# Copy_of_Copy_of_Sheet1.net
KiCad netlist of a schematic drawn in Altium Designer
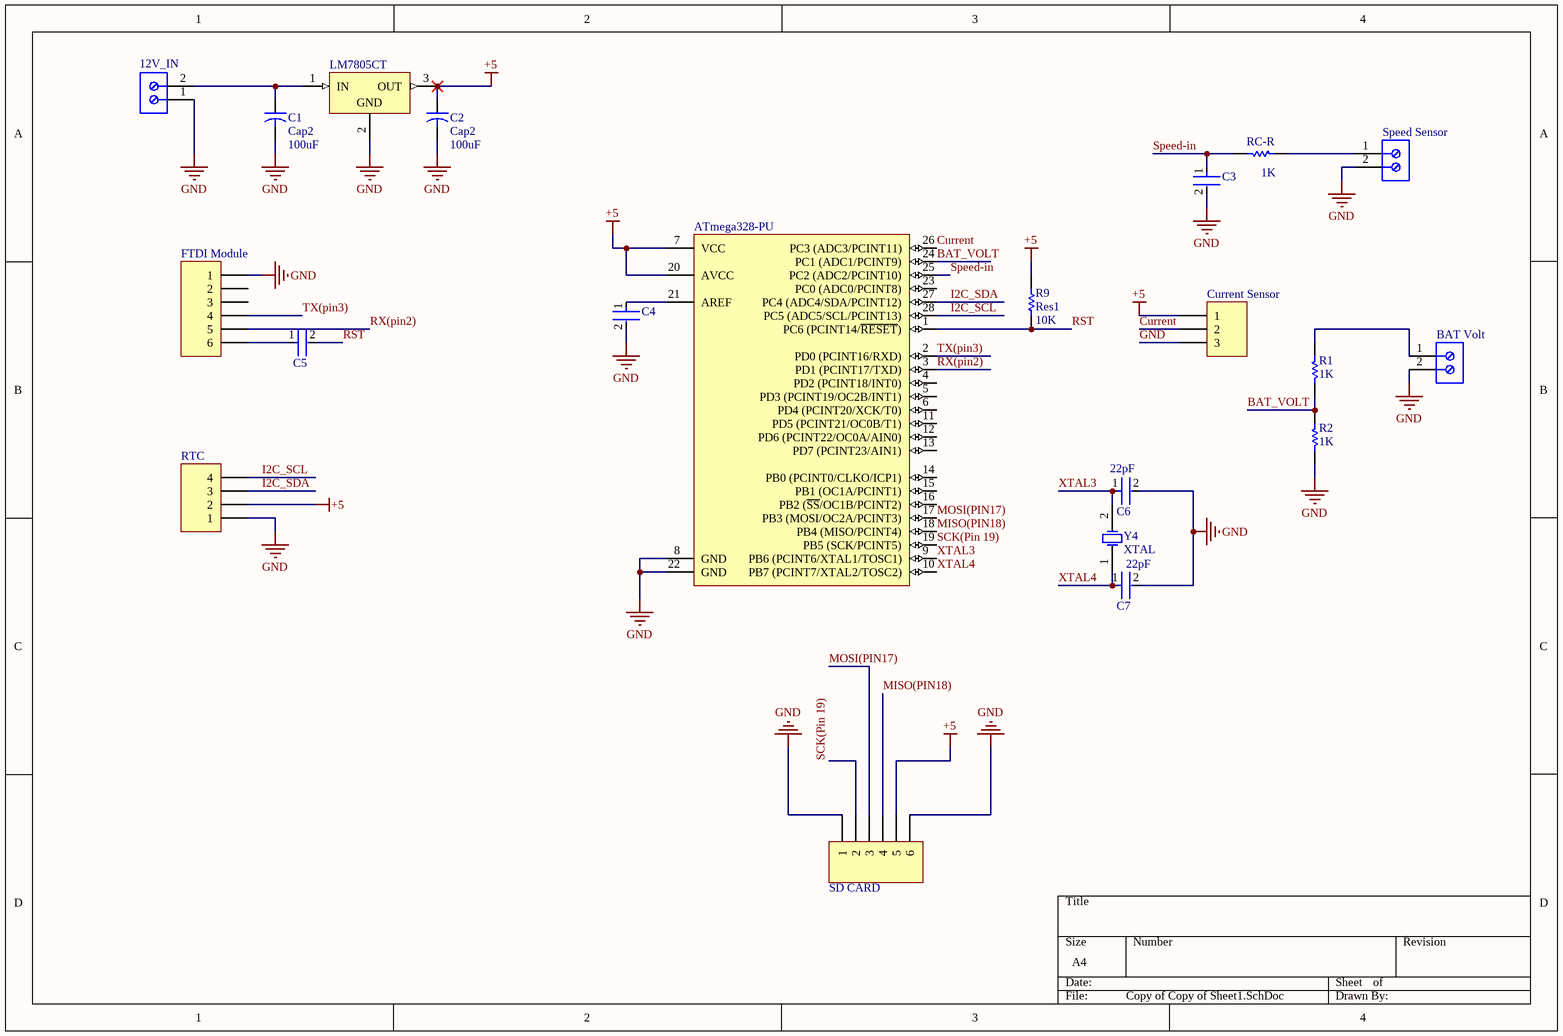
[diagram p0: Copy of Copy of Sheet1.SchDoc]

(export (version "E")
  (design (tool "Eeschema 10.0.6"))
  (components
    (comp (ref "12V_IN")
      (value "691213710002")
      (footprint "691213710002")
      (description "Serie 213 - 5.00 mm Horizontal Entry Modular with RisingCage Clamp WR-TBL, 2 pin")
      (fields (field (name "MANUFACTURER") "Wurth Elektronik") (field (name "PUBLISHER") "WurthElektronik"))
      (libsource (lib "Altium Content Vault") (part "WE-CN-1P-F-TB2"))
    )
    (comp (ref "ATmega328-PU")
      (value "ATmega328-PU")
      (footprint "28P3")
      (libsource (lib "Atmel Microcontroller megaAVR") (part "ATmega328-PU"))
    )
    (comp (ref "BAT Volt")
      (value "691213710002")
      (footprint "691213710002")
      (description "Serie 213 - 5.00 mm Horizontal Entry Modular with RisingCage Clamp WR-TBL, 2 pin")
      (fields (field (name "MANUFACTURER") "Wurth Elektronik") (field (name "PUBLISHER") "WurthElektronik"))
      (libsource (lib "Altium Content Vault") (part "WE-CN-1P-F-TB2"))
    )
    (comp (ref "C1")
      (value "Cap2")
      (footprint "CAPR5-4X5")
      (description "Capacitor")
      (fields (field (name "ALTIUM_VALUE") "100uF") (field (name "PUBLISHER") "Altium Limited"))
      (libsource (lib "Miscellaneous Devices") (part "Cap2"))
    )
    (comp (ref "C2")
      (value "Cap2")
      (footprint "CAPR5-4X5")
      (description "Capacitor")
      (fields (field (name "ALTIUM_VALUE") "100uF") (field (name "PUBLISHER") "Altium Limited"))
      (libsource (lib "Miscellaneous Devices") (part "Cap2"))
    )
    (comp (ref "C3")
      (value "100nF")
      (footprint "FP-K15H5-MFG")
      (description "CAP CER 0.1UF 50V X7R RADIAL")
      (fields (field (name "VOLTAGE") "50V") (field (name "TOLERANCE") "10%"))
      (libsource (lib "Altium Content Vault") (part "11868f565c42a9108669ba33697ecf6"))
    )
    (comp (ref "C4")
      (value "K104K15X7RF53H5")
      (footprint "FP-K15H5-MFG")
      (description "CAP CER 0.1UF 50V X7R RADIAL")
      (fields (field (name "VOLTAGE") "50V") (field (name "TOLERANCE") "10%"))
      (libsource (lib "Altium Content Vault") (part "11868f565c42a9108669ba33697ecf6"))
    )
    (comp (ref "C5")
      (value "K104K15X7RF53H5")
      (footprint "FP-K15H5-MFG")
      (description "CAP CER 0.1UF 50V X7R RADIAL")
      (fields (field (name "VOLTAGE") "50V") (field (name "TOLERANCE") "10%"))
      (libsource (lib "Altium Content Vault") (part "11868f565c42a9108669ba33697ecf6"))
    )
    (comp (ref "C6")
      (value "22pF")
      (footprint "FP-K15H5-MFG")
      (description "CAP CER 0.1UF 50V X7R RADIAL")
      (fields (field (name "VOLTAGE") "50V") (field (name "TOLERANCE") "10%"))
      (libsource (lib "Altium Content Vault") (part "11868f565c42a9108669ba33697ecf6"))
    )
    (comp (ref "C7")
      (value "22pF")
      (footprint "FP-K15H5-MFG")
      (description "CAP CER 0.1UF 50V X7R RADIAL")
      (fields (field (name "VOLTAGE") "50V") (field (name "TOLERANCE") "10%"))
      (libsource (lib "Altium Content Vault") (part "11868f565c42a9108669ba33697ecf6"))
    )
    (comp (ref "Current Sensor")
      (value "Current Sensor")
      (footprint "HDR1X3")
      (description "Header, 3-Pin")
      (fields (field (name "PUBLISHER") "Altium Limited"))
      (libsource (lib "Miscellaneous Connectors") (part "Header 3"))
    )
    (comp (ref "FTDI Module")
      (value "FTDI Module")
      (footprint "HDR1X6")
      (description "Header, 6-Pin")
      (fields (field (name "PUBLISHER") "Altium Limited"))
      (libsource (lib "") (part "Header 6_1"))
    )
    (comp (ref "LM7805CT")
      (value "LM7805CT")
      (footprint "FAIR-TO-220-3")
      (description "Positive Voltage Regulator, 5 V, 1 A, -40 to 125 degC, 3-Pin TO-220, RoHS, Tube")
      (fields (field (name "MANUFACTURER") "FairchildSemiconductor"))
      (libsource (lib "Altium Content Vault") (part "FAIR-LM7805CT-TO220-3"))
    )
    (comp (ref "R1")
      (value "1K")
      (footprint "AXIAL-0.3")
      (description "Resistor")
      (fields (field (name "Comment") "Res1") (field (name "PUBLISHER") "Altium Limited"))
      (libsource (lib "Miscellaneous Devices") (part "Res1"))
    )
    (comp (ref "R2")
      (value "1K")
      (footprint "AXIAL-0.3")
      (description "Resistor")
      (fields (field (name "Comment") "Res1") (field (name "PUBLISHER") "Altium Limited"))
      (libsource (lib "Miscellaneous Devices") (part "Res1"))
    )
    (comp (ref "R9")
      (value "Res1")
      (footprint "AXIAL-0.3")
      (description "Resistor")
      (fields (field (name "ALTIUM_VALUE") "10K") (field (name "PUBLISHER") "Altium Limited"))
      (libsource (lib "Miscellaneous Devices") (part "Res1"))
    )
    (comp (ref "RC-R")
      (value "1K")
      (footprint "AXIAL-0.3")
      (description "Resistor")
      (fields (field (name "Comment") "Res1") (field (name "PUBLISHER") "Altium Limited"))
      (libsource (lib "Miscellaneous Devices") (part "Res1"))
    )
    (comp (ref "RTC")
      (value "Header 4")
      (footprint "HDR1X4")
      (description "Header, 4-Pin")
      (fields (field (name "PUBLISHER") "Altium Limited"))
      (libsource (lib "Miscellaneous Connectors") (part "Header 4"))
    )
    (comp (ref "SD CARD")
      (value "SD CARD")
      (footprint "HDR1X6")
      (description "Header, 6-Pin")
      (fields (field (name "PUBLISHER") "Altium Limited"))
      (libsource (lib "Miscellaneous Connectors") (part "Header 6"))
    )
    (comp (ref "Speed Sensor")
      (value "Speed Sensor")
      (footprint "691213710002")
      (description "Serie 213 - 5.00 mm Horizontal Entry Modular with RisingCage Clamp WR-TBL, 2 pin")
      (fields
        (field (name "MANUFACTURER") "Wurth Elektronik")
        (field (name "PART NUMBER") "691213710002")
        (field (name "PUBLISHER") "WurthElektronik")
      )
      (libsource (lib "Altium Content Vault") (part "WE-CN-1P-F-TB2"))
    )
    (comp (ref "Y4")
      (value "XTAL")
      (footprint "R38")
      (description "Crystal Oscillator")
      (fields (field (name "PUBLISHER") "Altium Limited"))
      (libsource (lib "Miscellaneous Devices") (part "XTAL"))
    )
  )
  (nets
    (net (code "1") (name "+5") (class "Default")
      (node (ref "ATmega328-PU") (pin "20") (pinfunction "AVCC_20") (pintype "power_in"))
      (node (ref "ATmega328-PU") (pin "7") (pinfunction "VCC_7") (pintype "power_in"))
      (node (ref "C2") (pin "1") (pinfunction "1_1") (pintype "passive"))
      (node (ref "Current Sensor") (pin "1") (pinfunction "1_1") (pintype "passive"))
      (node (ref "LM7805CT") (pin "3") (pinfunction "OUT_3") (pintype "output"))
      (node (ref "R9") (pin "1") (pinfunction "1_1") (pintype "passive"))
      (node (ref "RTC") (pin "2") (pinfunction "2_2") (pintype "passive"))
      (node (ref "SD CARD") (pin "5") (pinfunction "5_5") (pintype "passive"))
    )
    (net (code "2") (name "/BAT_VOLT") (class "Default")
      (node (ref "ATmega328-PU") (pin "24") (pinfunction "PC1_(ADC1/PCINT9)_24") (pintype "bidirectional"))
      (node (ref "R1") (pin "2") (pinfunction "2_2") (pintype "passive"))
      (node (ref "R2") (pin "1") (pinfunction "1_1") (pintype "passive"))
    )
    (net (code "3") (name "/Current") (class "Default")
      (node (ref "ATmega328-PU") (pin "26") (pinfunction "PC3_(ADC3/PCINT11)_26") (pintype "bidirectional"))
      (node (ref "Current Sensor") (pin "2") (pinfunction "2_2") (pintype "passive"))
    )
    (net (code "4") (name "/I2C_SCL") (class "Default")
      (node (ref "ATmega328-PU") (pin "28") (pinfunction "PC5_(ADC5/SCL/PCINT13)_28") (pintype "bidirectional"))
      (node (ref "RTC") (pin "4") (pinfunction "4_4") (pintype "passive"))
    )
    (net (code "5") (name "/I2C_SDA") (class "Default")
      (node (ref "ATmega328-PU") (pin "27") (pinfunction "PC4_(ADC4/SDA/PCINT12)_27") (pintype "bidirectional"))
      (node (ref "RTC") (pin "3") (pinfunction "3_3") (pintype "passive"))
    )
    (net (code "6") (name "/MISO(PIN18)") (class "Default")
      (node (ref "ATmega328-PU") (pin "18") (pinfunction "PB4_(MISO/PCINT4)_18") (pintype "bidirectional"))
      (node (ref "SD CARD") (pin "4") (pinfunction "4_4") (pintype "passive"))
    )
    (net (code "7") (name "/MOSI(PIN17)") (class "Default")
      (node (ref "ATmega328-PU") (pin "17") (pinfunction "PB3_(MOSI/OC2A/PCINT3)_17") (pintype "bidirectional"))
      (node (ref "SD CARD") (pin "3") (pinfunction "3_3") (pintype "passive"))
    )
    (net (code "8") (name "/RST") (class "Default")
      (node (ref "ATmega328-PU") (pin "1") (pinfunction "PC6_(PCINT14/~{RESET})_1") (pintype "bidirectional"))
      (node (ref "C5") (pin "2") (pinfunction "2_2") (pintype "passive"))
      (node (ref "R9") (pin "2") (pinfunction "2_2") (pintype "passive"))
    )
    (net (code "9") (name "/RX(pin2)") (class "Default")
      (node (ref "ATmega328-PU") (pin "3") (pinfunction "PD1_(PCINT17/TXD)_3") (pintype "bidirectional"))
      (node (ref "FTDI Module") (pin "5") (pinfunction "5_5") (pintype "passive"))
    )
    (net (code "10") (name "/SCK(Pin 19)") (class "Default")
      (node (ref "ATmega328-PU") (pin "19") (pinfunction "PB5_(SCK/PCINT5)_19") (pintype "bidirectional"))
      (node (ref "SD CARD") (pin "2") (pinfunction "2_2") (pintype "passive"))
    )
    (net (code "11") (name "/Speed-in") (class "Default")
      (node (ref "ATmega328-PU") (pin "25") (pinfunction "PC2_(ADC2/PCINT10)_25") (pintype "bidirectional"))
      (node (ref "C3") (pin "1") (pinfunction "1_1") (pintype "passive"))
      (node (ref "RC-R") (pin "2") (pinfunction "2_2") (pintype "passive"))
    )
    (net (code "12") (name "/TX(pin3)") (class "Default")
      (node (ref "ATmega328-PU") (pin "2") (pinfunction "PD0_(PCINT16/RXD)_2") (pintype "bidirectional"))
      (node (ref "FTDI Module") (pin "4") (pinfunction "4_4") (pintype "passive"))
    )
    (net (code "13") (name "/XTAL3") (class "Default")
      (node (ref "ATmega328-PU") (pin "9") (pinfunction "PB6_(PCINT6/XTAL1/TOSC1)_9") (pintype "bidirectional"))
      (node (ref "C6") (pin "1") (pinfunction "1_1") (pintype "passive"))
      (node (ref "Y4") (pin "2") (pinfunction "OSC2_2") (pintype "passive"))
    )
    (net (code "14") (name "/XTAL4") (class "Default")
      (node (ref "ATmega328-PU") (pin "10") (pinfunction "PB7_(PCINT7/XTAL2/TOSC2)_10") (pintype "bidirectional"))
      (node (ref "C7") (pin "1") (pinfunction "1_1") (pintype "passive"))
      (node (ref "Y4") (pin "1") (pinfunction "OSC1_1") (pintype "passive"))
    )
    (net (code "15") (name "GND") (class "Default")
      (node (ref "12V_IN") (pin "1") (pinfunction "1_1") (pintype "passive"))
      (node (ref "ATmega328-PU") (pin "22") (pinfunction "GND_22") (pintype "power_in"))
      (node (ref "ATmega328-PU") (pin "8") (pinfunction "GND_8") (pintype "power_in"))
      (node (ref "BAT Volt") (pin "2") (pinfunction "2_2") (pintype "passive"))
      (node (ref "C1") (pin "2") (pinfunction "2_2") (pintype "passive"))
      (node (ref "C2") (pin "2") (pinfunction "2_2") (pintype "passive"))
      (node (ref "C3") (pin "2") (pinfunction "2_2") (pintype "passive"))
      (node (ref "C4") (pin "2") (pinfunction "2_2") (pintype "passive"))
      (node (ref "C6") (pin "2") (pinfunction "2_2") (pintype "passive"))
      (node (ref "C7") (pin "2") (pinfunction "2_2") (pintype "passive"))
      (node (ref "Current Sensor") (pin "3") (pinfunction "3_3") (pintype "passive"))
      (node (ref "FTDI Module") (pin "1") (pinfunction "1_1") (pintype "passive"))
      (node (ref "LM7805CT") (pin "2") (pinfunction "GND_2") (pintype "power_in"))
      (node (ref "R2") (pin "2") (pinfunction "2_2") (pintype "passive"))
      (node (ref "RTC") (pin "1") (pinfunction "1_1") (pintype "passive"))
      (node (ref "SD CARD") (pin "1") (pinfunction "1_1") (pintype "passive"))
      (node (ref "SD CARD") (pin "6") (pinfunction "6_6") (pintype "passive"))
      (node (ref "Speed Sensor") (pin "2") (pinfunction "2_2") (pintype "passive"))
    )
    (net (code "16") (name "Net-(ATmega328-PU-AREF)") (class "Default")
      (node (ref "ATmega328-PU") (pin "21") (pinfunction "AREF_21") (pintype "power_in"))
      (node (ref "C4") (pin "1") (pinfunction "1_1") (pintype "passive"))
    )
    (net (code "17") (name "Net-(BAT Volt-Pad1)") (class "Default")
      (node (ref "BAT Volt") (pin "1") (pinfunction "1_1") (pintype "passive"))
      (node (ref "R1") (pin "1") (pinfunction "1_1") (pintype "passive"))
    )
    (net (code "18") (name "Net-(C5-Pad1)") (class "Default")
      (node (ref "C5") (pin "1") (pinfunction "1_1") (pintype "passive"))
      (node (ref "FTDI Module") (pin "6") (pinfunction "6_6") (pintype "passive"))
    )
    (net (code "19") (name "Net-(LM7805CT-IN)") (class "Default")
      (node (ref "12V_IN") (pin "2") (pinfunction "2_2") (pintype "passive"))
      (node (ref "C1") (pin "1") (pinfunction "1_1") (pintype "passive"))
      (node (ref "LM7805CT") (pin "1") (pinfunction "IN_1") (pintype "input"))
    )
    (net (code "20") (name "Net-(RC-R-Pad1)") (class "Default")
      (node (ref "RC-R") (pin "1") (pinfunction "1_1") (pintype "passive"))
      (node (ref "Speed Sensor") (pin "1") (pinfunction "1_1") (pintype "passive"))
    )
    (net (code "21") (name "unconnected-(ATmega328-PU-PB0_(PCINT0{slash}CLKO{slash}ICP1)-Pad14)") (class "Default")
      (node (ref "ATmega328-PU") (pin "14") (pinfunction "PB0_(PCINT0/CLKO/ICP1)_14") (pintype "bidirectional"))
    )
    (net (code "22") (name "unconnected-(ATmega328-PU-PB1_(OC1A{slash}PCINT1)-Pad15)") (class "Default")
      (node (ref "ATmega328-PU") (pin "15") (pinfunction "PB1_(OC1A/PCINT1)_15") (pintype "bidirectional"))
    )
    (net (code "23") (name "unconnected-(ATmega328-PU-PB2_(~{SS}{slash}OC1B{slash}PCINT2)-Pad16)") (class "Default")
      (node (ref "ATmega328-PU") (pin "16") (pinfunction "PB2_(~{SS}/OC1B/PCINT2)_16") (pintype "bidirectional"))
    )
    (net (code "24") (name "unconnected-(ATmega328-PU-PC0_(ADC0{slash}PCINT8)-Pad23)") (class "Default")
      (node (ref "ATmega328-PU") (pin "23") (pinfunction "PC0_(ADC0/PCINT8)_23") (pintype "bidirectional"))
    )
    (net (code "25") (name "unconnected-(ATmega328-PU-PD2_(PCINT18{slash}INT0)-Pad4)") (class "Default")
      (node (ref "ATmega328-PU") (pin "4") (pinfunction "PD2_(PCINT18/INT0)_4") (pintype "bidirectional"))
    )
    (net (code "26") (name "unconnected-(ATmega328-PU-PD3_(PCINT19{slash}OC2B{slash}INT1)-Pad5)") (class "Default")
      (node (ref "ATmega328-PU") (pin "5") (pinfunction "PD3_(PCINT19/OC2B/INT1)_5") (pintype "bidirectional"))
    )
    (net (code "27") (name "unconnected-(ATmega328-PU-PD4_(PCINT20{slash}XCK{slash}T0)-Pad6)") (class "Default")
      (node (ref "ATmega328-PU") (pin "6") (pinfunction "PD4_(PCINT20/XCK/T0)_6") (pintype "bidirectional"))
    )
    (net (code "28") (name "unconnected-(ATmega328-PU-PD5_(PCINT21{slash}OC0B{slash}T1)-Pad11)") (class "Default")
      (node (ref "ATmega328-PU") (pin "11") (pinfunction "PD5_(PCINT21/OC0B/T1)_11") (pintype "bidirectional"))
    )
    (net (code "29") (name "unconnected-(ATmega328-PU-PD6_(PCINT22{slash}OC0A{slash}AIN0)-Pad12)") (class "Default")
      (node (ref "ATmega328-PU") (pin "12") (pinfunction "PD6_(PCINT22/OC0A/AIN0)_12") (pintype "bidirectional"))
    )
    (net (code "30") (name "unconnected-(ATmega328-PU-PD7_(PCINT23{slash}AIN1)-Pad13)") (class "Default")
      (node (ref "ATmega328-PU") (pin "13") (pinfunction "PD7_(PCINT23/AIN1)_13") (pintype "bidirectional"))
    )
    (net (code "31") (name "unconnected-(FTDI Module-Pad2)") (class "Default")
      (node (ref "FTDI Module") (pin "2") (pinfunction "2_2") (pintype "passive"))
    )
    (net (code "32") (name "unconnected-(FTDI Module-Pad3)") (class "Default")
      (node (ref "FTDI Module") (pin "3") (pinfunction "3_3") (pintype "passive"))
    )
  )
)
